# 3_USB.net
KiCad netlist of a schematic drawn in Altium Designer
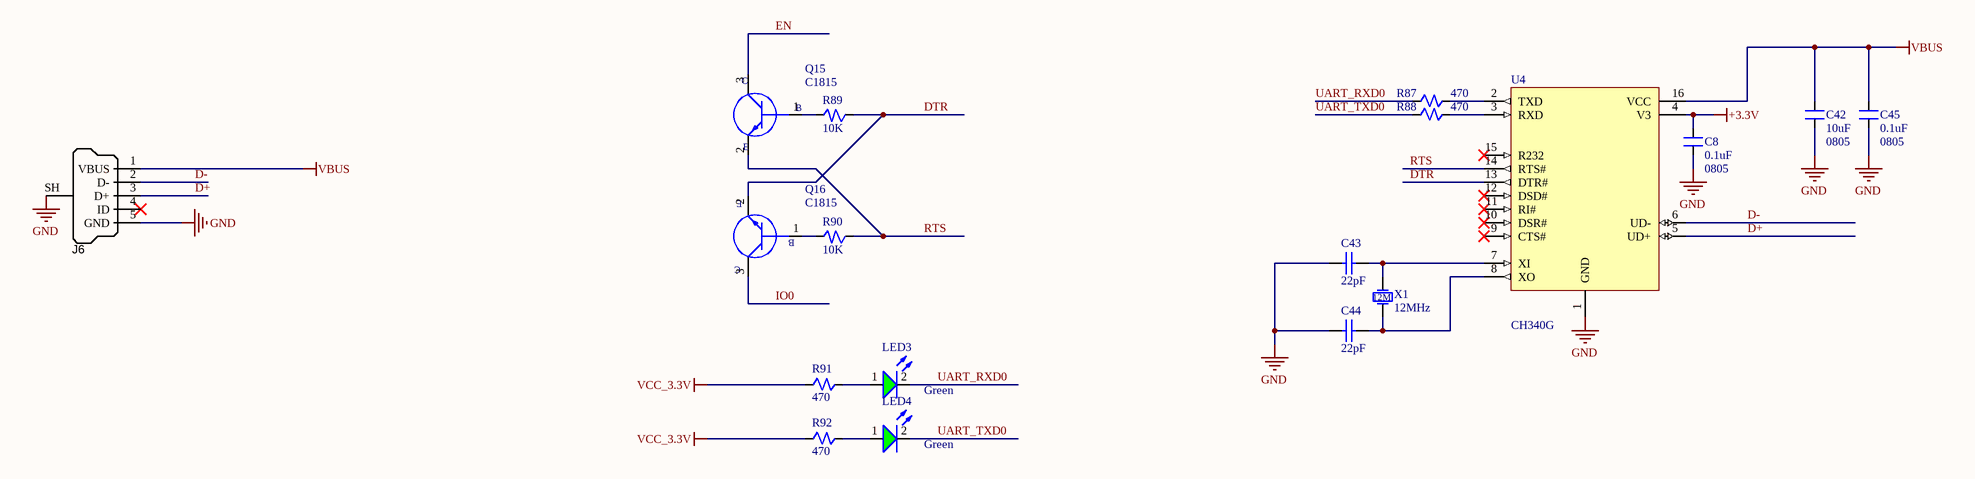
[diagram p0: [3] USB.SchDoc]

(export (version "E")
  (design (tool "Eeschema 10.0.6"))
  (components
    (comp (ref "C8")
      (value "0.1uF")
      (footprint "SM-0805")
      (description "CAP 0805")
      (fields (field (name "PACKAGE/CASE") "0805"))
      (libsource (lib "DIEN TU HELLO") (part "Cap 0805_1"))
    )
    (comp (ref "C42")
      (value "10uF")
      (footprint "SM-0805")
      (description "CAP 0805")
      (fields (field (name "PACKAGE/CASE") "0805"))
      (libsource (lib "DIEN TU HELLO") (part "Cap 0805_1"))
    )
    (comp (ref "C43")
      (value "22pF")
      (footprint "tu 0805")
      (description "Dán")
      (libsource (lib "DIEN TU HELLO") (part "Tu 0805 22pF 50V 10%"))
    )
    (comp (ref "C44")
      (value "22pF")
      (footprint "tu 0805")
      (description "Dán")
      (libsource (lib "DIEN TU HELLO") (part "Tu 0805 22pF 50V 10%"))
    )
    (comp (ref "C45")
      (value "0.1uF")
      (footprint "SM-0805")
      (description "CAP 0805")
      (fields (field (name "PACKAGE/CASE") "0805"))
      (libsource (lib "DIEN TU HELLO") (part "Cap 0805_1"))
    )
    (comp (ref "J6")
      (value "USB Micro Type B (recommended if hand soldering)")
      (footprint "USB_Micro-B_FCI_SMD")
      (description "Connector SMD-THD USB Micro Type B middle mount")
      (libsource (lib "DIEN TU HELLO") (part "USB_Micro_TypeB_FCI"))
    )
    (comp (ref "LED3")
      (value "Green")
      (footprint "Led 0805G")
      (description "LED Green 2mA 3V 0805")
      (fields (field (name "Comment") "LED-0805GVC"))
      (libsource (lib "lpson") (part "LED-0805GVC"))
    )
    (comp (ref "LED4")
      (value "Green")
      (footprint "Led 0805G")
      (description "LED Green 2mA 3V 0805")
      (fields (field (name "Comment") "LED-0805GVC"))
      (libsource (lib "lpson") (part "LED-0805GVC"))
    )
    (comp (ref "Q15")
      (value "C1815")
      (footprint "SOT23-132")
      (description "TRANS C1815 SOT23 TRANS NPN 0.15A 50V")
      (fields (field (name "MANUFACTURER") "Minh Hà") (field (name "VOLTAGE") "45V"))
      (libsource (lib "DIEN TU HELLO") (part "C1815 SMD"))
    )
    (comp (ref "Q16")
      (value "C1815")
      (footprint "SOT23-132")
      (description "TRANS C1815 SOT23 TRANS NPN 0.15A 50V")
      (fields (field (name "MANUFACTURER") "Minh Hà") (field (name "VOLTAGE") "45V"))
      (libsource (lib "DIEN TU HELLO") (part "C1815 SMD"))
    )
    (comp (ref "R87")
      (value "470")
      (footprint "RES_0805")
      (description "Điện Trở 470 Ohm 0805 1% 1/8W")
      (fields (field (name "PART NUMBER") "Trở 0805 1% 470R") (field (name "MANUFACTURER") "Minh Hà"))
      (libsource (lib "DIEN TU HELLO") (part "RES 470R 0805 1% 1/8W"))
    )
    (comp (ref "R88")
      (value "470")
      (footprint "RES_0805")
      (description "Điện Trở 470 Ohm 0805 1% 1/8W")
      (fields (field (name "PART NUMBER") "Trở 0805 1% 470R") (field (name "MANUFACTURER") "Minh Hà"))
      (libsource (lib "DIEN TU HELLO") (part "RES 470R 0805 1% 1/8W"))
    )
    (comp (ref "R89")
      (value "10K")
      (footprint "RES_0805")
      (description "Điện Trở 10 KOhm 0805 1% 1/8W")
      (fields (field (name "PART NUMBER") "Trở 0805 1% 10K") (field (name "MANUFACTURER") "Minh Hà"))
      (libsource (lib "DIEN TU HELLO") (part "RES 10K 0805 1% 1/8W"))
    )
    (comp (ref "R90")
      (value "10K")
      (footprint "RES_0805")
      (description "Điện Trở 10 KOhm 0805 1% 1/8W")
      (fields (field (name "PART NUMBER") "Trở 0805 1% 10K") (field (name "MANUFACTURER") "Minh Hà"))
      (libsource (lib "DIEN TU HELLO") (part "RES 10K 0805 1% 1/8W"))
    )
    (comp (ref "R91")
      (value "470")
      (footprint "RES_0805")
      (description "Điện Trở 470 Ohm 0805 1% 1/8W")
      (fields (field (name "PART NUMBER") "Trở 0805 1% 470R") (field (name "MANUFACTURER") "Minh Hà"))
      (libsource (lib "DIEN TU HELLO") (part "RES 470R 0805 1% 1/8W"))
    )
    (comp (ref "R92")
      (value "470")
      (footprint "RES_0805")
      (description "Điện Trở 470 Ohm 0805 1% 1/8W")
      (fields (field (name "PART NUMBER") "Trở 0805 1% 470R") (field (name "MANUFACTURER") "Minh Hà"))
      (libsource (lib "DIEN TU HELLO") (part "RES 470R 0805 1% 1/8W"))
    )
    (comp (ref "U4")
      (value "CH340G")
      (footprint "CH340G")
      (description "USB to serial chip CH340")
      (libsource (lib "DIEN TU HELLO") (part "CH340G"))
    )
    (comp (ref "X1")
      (value "12MHz")
      (footprint "CRYSTAL_ABM3 5x3.2mm")
      (description "CRYSTAL 12.0000MHZ 18pF SMD")
      (fields (field (name "PART NUMBER") "ABM3-12.000MHZ-D2Y-T") (field (name "MANUFACTURER") "Abracon"))
      (libsource (lib "DIEN TU HELLO") (part "ABM3-12.000MHZ-D2Y-T"))
    )
  )
  (nets
    (net (code "1") (name "+3.3V") (class "Default")
      (node (ref "C8") (pin "2") (pinfunction "2_2") (pintype "passive"))
      (node (ref "U4") (pin "4") (pinfunction "V3_4") (pintype "power_in"))
    )
    (net (code "2") (name "/D+") (class "Default")
      (node (ref "J6") (pin "3") (pinfunction "D+_3") (pintype "passive"))
      (node (ref "U4") (pin "5") (pinfunction "UD+_5") (pintype "bidirectional"))
    )
    (net (code "3") (name "/D-") (class "Default")
      (node (ref "J6") (pin "2") (pinfunction "D-_2") (pintype "passive"))
      (node (ref "U4") (pin "6") (pinfunction "UD-_6") (pintype "bidirectional"))
    )
    (net (code "4") (name "/DTR") (class "Default")
      (node (ref "Q16") (pin "2") (pinfunction "E_2") (pintype "passive"))
      (node (ref "R89") (pin "1") (pinfunction "1_1") (pintype "passive"))
      (node (ref "U4") (pin "13") (pinfunction "DTR#_13") (pintype "output"))
    )
    (net (code "5") (name "/EN") (class "Default")
      (node (ref "Q15") (pin "3") (pinfunction "C_3") (pintype "passive"))
    )
    (net (code "6") (name "/IO0") (class "Default")
      (node (ref "Q16") (pin "3") (pinfunction "C_3") (pintype "passive"))
    )
    (net (code "7") (name "/RTS") (class "Default")
      (node (ref "Q15") (pin "2") (pinfunction "E_2") (pintype "passive"))
      (node (ref "R90") (pin "1") (pinfunction "1_1") (pintype "passive"))
      (node (ref "U4") (pin "14") (pinfunction "RTS#_14") (pintype "output"))
    )
    (net (code "8") (name "/UART_RXD0") (class "Default")
      (node (ref "LED3") (pin "2") (pinfunction "K_2") (pintype "passive"))
      (node (ref "R87") (pin "1") (pinfunction "1_1") (pintype "passive"))
    )
    (net (code "9") (name "/UART_TXD0") (class "Default")
      (node (ref "LED4") (pin "2") (pinfunction "K_2") (pintype "passive"))
      (node (ref "R88") (pin "1") (pinfunction "1_1") (pintype "passive"))
    )
    (net (code "10") (name "GND") (class "Default")
      (node (ref "C42") (pin "1") (pinfunction "1_1") (pintype "passive"))
      (node (ref "C43") (pin "2") (pinfunction "2_2") (pintype "passive"))
      (node (ref "C44") (pin "1") (pinfunction "1_1") (pintype "passive"))
      (node (ref "C45") (pin "1") (pinfunction "1_1") (pintype "passive"))
      (node (ref "C8") (pin "1") (pinfunction "1_1") (pintype "passive"))
      (node (ref "J6") (pin "5") (pinfunction "GND_5") (pintype "passive"))
      (node (ref "J6") (pin "SH") (pinfunction "Shell_SH") (pintype "passive"))
      (node (ref "U4") (pin "1") (pinfunction "GND_1") (pintype "power_in"))
    )
    (net (code "11") (name "Net-(LED3-A)") (class "Default")
      (node (ref "LED3") (pin "1") (pinfunction "A_1") (pintype "passive"))
      (node (ref "R91") (pin "2") (pinfunction "2_2") (pintype "passive"))
    )
    (net (code "12") (name "Net-(LED4-A)") (class "Default")
      (node (ref "LED4") (pin "1") (pinfunction "A_1") (pintype "passive"))
      (node (ref "R92") (pin "2") (pinfunction "2_2") (pintype "passive"))
    )
    (net (code "13") (name "Net-(Q15-B)") (class "Default")
      (node (ref "Q15") (pin "1") (pinfunction "B_1") (pintype "passive"))
      (node (ref "R89") (pin "2") (pinfunction "2_2") (pintype "passive"))
    )
    (net (code "14") (name "Net-(Q16-B)") (class "Default")
      (node (ref "Q16") (pin "1") (pinfunction "B_1") (pintype "passive"))
      (node (ref "R90") (pin "2") (pinfunction "2_2") (pintype "passive"))
    )
    (net (code "15") (name "Net-(U4-RXD)") (class "Default")
      (node (ref "R88") (pin "2") (pinfunction "2_2") (pintype "passive"))
      (node (ref "U4") (pin "3") (pinfunction "RXD_3") (pintype "input"))
    )
    (net (code "16") (name "Net-(U4-TXD)") (class "Default")
      (node (ref "R87") (pin "2") (pinfunction "2_2") (pintype "passive"))
      (node (ref "U4") (pin "2") (pinfunction "TXD_2") (pintype "output"))
    )
    (net (code "17") (name "Net-(U4-XI)") (class "Default")
      (node (ref "C43") (pin "1") (pinfunction "1_1") (pintype "passive"))
      (node (ref "U4") (pin "7") (pinfunction "XI_7") (pintype "input"))
      (node (ref "X1") (pin "1") (pinfunction "OSC1_1") (pintype "passive"))
    )
    (net (code "18") (name "Net-(U4-XO)") (class "Default")
      (node (ref "C44") (pin "2") (pinfunction "2_2") (pintype "passive"))
      (node (ref "U4") (pin "8") (pinfunction "XO_8") (pintype "output"))
      (node (ref "X1") (pin "2") (pinfunction "OSC2_2") (pintype "passive"))
    )
    (net (code "19") (name "VBUS") (class "Default")
      (node (ref "C42") (pin "2") (pinfunction "2_2") (pintype "passive"))
      (node (ref "C45") (pin "2") (pinfunction "2_2") (pintype "passive"))
      (node (ref "J6") (pin "1") (pinfunction "VBUS_1") (pintype "passive"))
      (node (ref "U4") (pin "16") (pinfunction "VCC_16") (pintype "power_in"))
    )
    (net (code "20") (name "VCC_3.3V") (class "Default")
      (node (ref "R91") (pin "1") (pinfunction "1_1") (pintype "passive"))
      (node (ref "R92") (pin "1") (pinfunction "1_1") (pintype "passive"))
    )
    (net (code "21") (name "unconnected-(J6-ID-Pad4)") (class "Default")
      (node (ref "J6") (pin "4") (pinfunction "ID_4") (pintype "passive+no_connect"))
    )
    (net (code "22") (name "unconnected-(U4-CTS#-Pad9)") (class "Default")
      (node (ref "U4") (pin "9") (pinfunction "CTS#_9") (pintype "input+no_connect"))
    )
    (net (code "23") (name "unconnected-(U4-DSD#-Pad12)") (class "Default")
      (node (ref "U4") (pin "12") (pinfunction "DSD#_12") (pintype "input+no_connect"))
    )
    (net (code "24") (name "unconnected-(U4-DSR#-Pad10)") (class "Default")
      (node (ref "U4") (pin "10") (pinfunction "DSR#_10") (pintype "input+no_connect"))
    )
    (net (code "25") (name "unconnected-(U4-R232-Pad15)") (class "Default")
      (node (ref "U4") (pin "15") (pinfunction "R232_15") (pintype "input+no_connect"))
    )
    (net (code "26") (name "unconnected-(U4-RI#-Pad11)") (class "Default")
      (node (ref "U4") (pin "11") (pinfunction "RI#_11") (pintype "input+no_connect"))
    )
  )
)
